# DIOT_template.net
KiCad netlist of a schematic drawn in Altium Designer
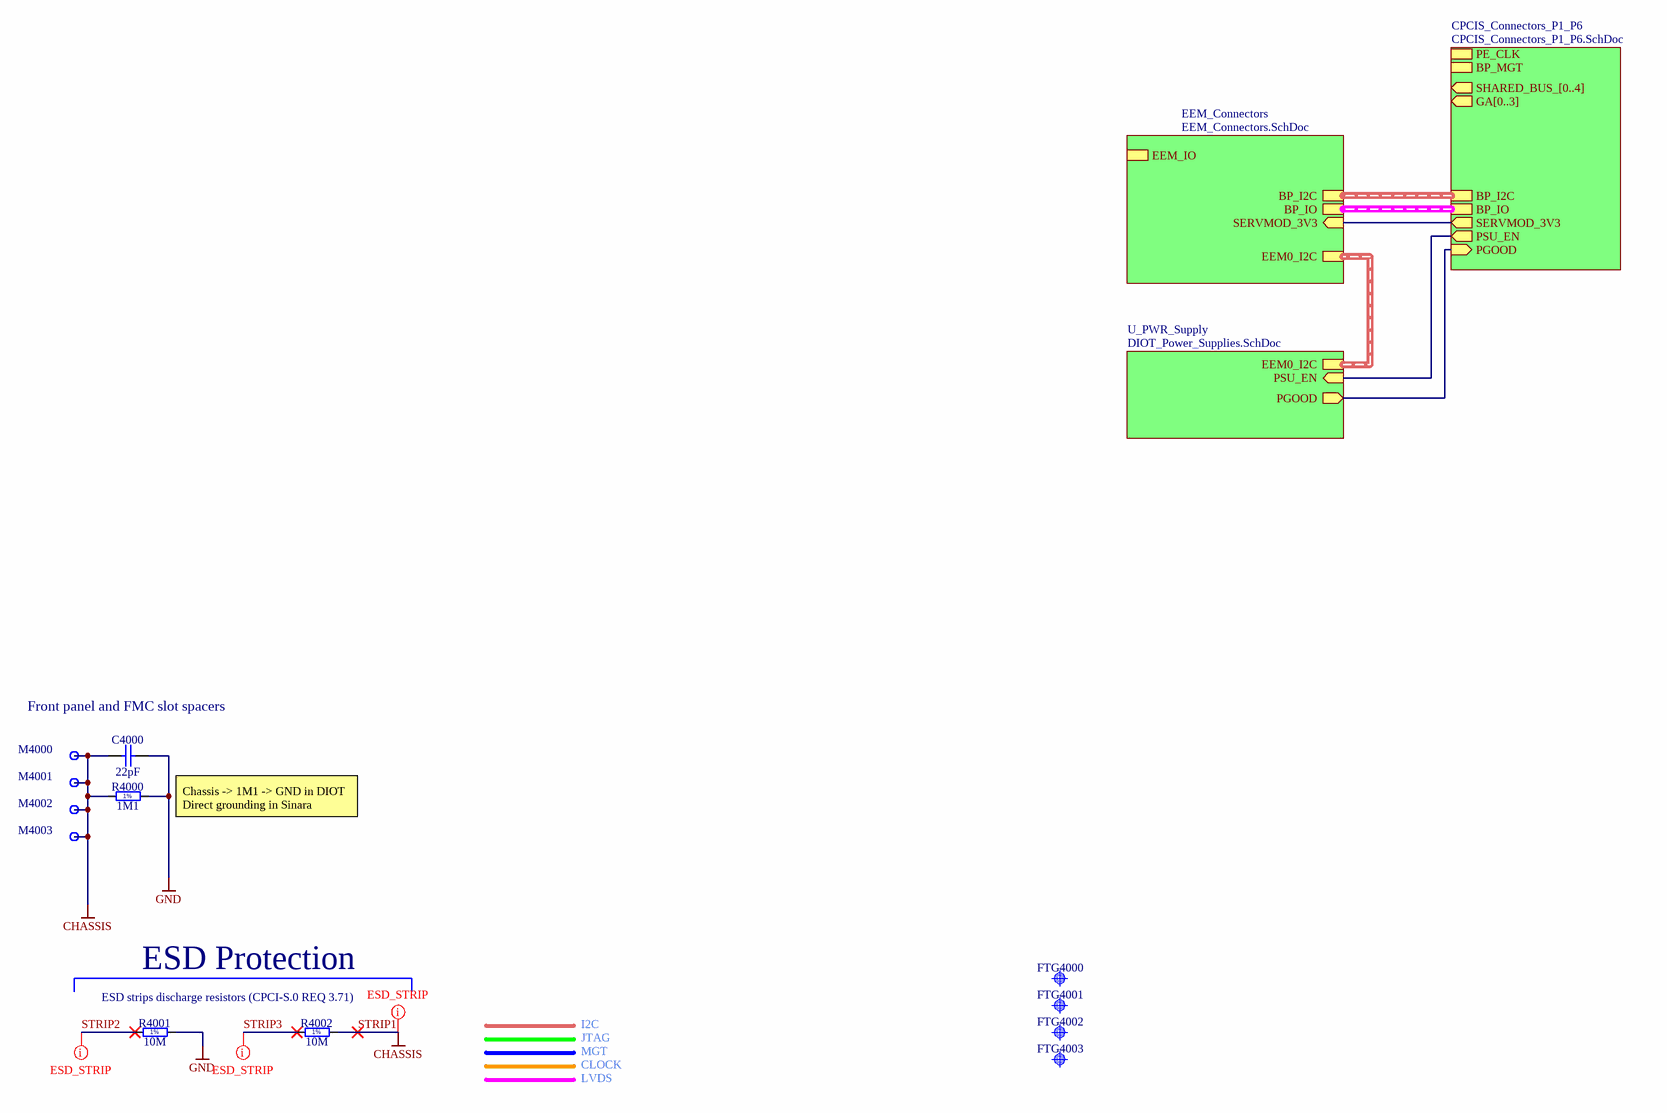
[diagram p0: DIOT_template.SchDoc]

(export (version "E")
  (design (tool "Eeschema 10.0.6"))
  (components
    (comp (ref "C4000")
      (value "22pF")
      (footprint "CAPC1005X55N")
      (description "Non-polarised capacitor")
      (fields
        (field (name "PART NUMBER") "CC0402_22PF_50V_5%_C0G")
        (field (name "VOLTAGE") "50V")
        (field (name "AUTHOR") "CERN DEM JLC")
      )
      (libsource (lib "Capacitors") (part "Capacitor - non polarized"))
    )
    (comp (ref "FTG4000")
      (value "Use only in PCB")
      (footprint "FIDUCIAL_TOP_C100-200")
      (description "Fiducial Target")
      (fields (field (name "PART NUMBER") "FIDUCIAL_TARGET_C100-200") (field (name "AUTHOR") "CERN DEM JLC"))
      (libsource (lib "Eletro-mechanical") (part "Fiducial Target"))
    )
    (comp (ref "FTG4001")
      (value "Use only in PCB")
      (footprint "FIDUCIAL_TOP_S100-200")
      (description "Fiducial Target")
      (fields (field (name "PART NUMBER") "FIDUCIAL_TARGET_S100-200") (field (name "AUTHOR") "CERN DEM JLC"))
      (libsource (lib "Eletro-mechanical") (part "Fiducial Target"))
    )
    (comp (ref "FTG4002")
      (value "Use only in PCB")
      (footprint "FIDUCIAL_TOP_S100-200")
      (description "Fiducial Target")
      (fields (field (name "PART NUMBER") "FIDUCIAL_TARGET_S100-200") (field (name "AUTHOR") "CERN DEM JLC"))
      (libsource (lib "Eletro-mechanical") (part "Fiducial Target"))
    )
    (comp (ref "FTG4003")
      (value "Use only in PCB")
      (footprint "FIDUCIAL_TOP_S100-200")
      (description "Fiducial Target")
      (fields (field (name "PART NUMBER") "FIDUCIAL_TARGET_S100-200") (field (name "AUTHOR") "CERN DEM JLC"))
      (libsource (lib "Eletro-mechanical") (part "Fiducial Target"))
    )
    (comp (ref "M4000")
      (value "Plated Hole")
      (footprint "MTG300_600")
      (description "Single Terminal Socket")
      (fields (field (name "PART NUMBER") "PLATED_HOLE3.0_PAD6.0") (field (name "AUTHOR") "CERN DEM JLC"))
      (libsource (lib "Eletro-mechanical") (part "Single Terminal Socket"))
    )
    (comp (ref "M4001")
      (value "Plated Hole")
      (footprint "MTG300_600")
      (description "Single Terminal Socket")
      (fields (field (name "PART NUMBER") "PLATED_HOLE3.0_PAD6.0") (field (name "AUTHOR") "CERN DEM JLC"))
      (libsource (lib "Eletro-mechanical") (part "Single Terminal Socket"))
    )
    (comp (ref "M4002")
      (value "Plated Hole")
      (footprint "MTG300_600")
      (description "Single Terminal Socket")
      (fields (field (name "PART NUMBER") "PLATED_HOLE3.0_PAD6.0") (field (name "AUTHOR") "CERN DEM JLC"))
      (libsource (lib "Eletro-mechanical") (part "Single Terminal Socket"))
    )
    (comp (ref "M4003")
      (value "Plated Hole")
      (footprint "MTG300_600")
      (description "Single Terminal Socket")
      (fields (field (name "PART NUMBER") "PLATED_HOLE3.0_PAD6.0") (field (name "AUTHOR") "CERN DEM JLC"))
      (libsource (lib "Eletro-mechanical") (part "Single Terminal Socket"))
    )
    (comp (ref "R4000")
      (value "1M1")
      (footprint "RESC2012X60N")
      (description "Resistor - 1%")
      (fields
        (field (name "PART NUMBER") "R0805_1M1_1%_0.125W_100PPM")
        (field (name "MANUFACTURER") "GENERIC")
        (field (name "AUTHOR") "CERN DEM JLC")
      )
      (libsource (lib "Resistors") (part "Resistor - 1%"))
    )
    (comp (ref "R4001")
      (value "10M")
      (footprint "RESC2113X55N")
      (description "Resistor - 1%")
      (fields
        (field (name "PART NUMBER") "R0805_10M_1%_0.125W_100PPM_VISHAY_CRCW e3")
        (field (name "POWER") "0.125W")
        (field (name "AUTHOR") "CERN DEM BC")
      )
      (libsource (lib "Resistors") (part "Resistor - 1%"))
    )
    (comp (ref "R4002")
      (value "10M")
      (footprint "RESC2113X55N")
      (description "Resistor - 1%")
      (fields
        (field (name "PART NUMBER") "R0805_10M_1%_0.125W_100PPM_VISHAY_CRCW e3")
        (field (name "POWER") "0.125W")
        (field (name "AUTHOR") "CERN DEM BC")
      )
      (libsource (lib "Resistors") (part "Resistor - 1%"))
    )
  )
  (nets
    (net (code "13") (name "/STRIP2") (class "Default")
      (node (ref "R4001") (pin "1") (pinfunction "1_1") (pintype "passive+no_connect"))
    )
    (net (code "14") (name "/STRIP3") (class "Default")
      (node (ref "R4002") (pin "1") (pinfunction "1_1") (pintype "passive+no_connect"))
    )
    (net (code "15") (name "CHASSIS") (class "Default")
      (node (ref "C4000") (pin "1") (pinfunction "1_1") (pintype "passive"))
      (node (ref "M4000") (pin "1") (pinfunction "1_1") (pintype "bidirectional"))
      (node (ref "M4001") (pin "1") (pinfunction "1_1") (pintype "bidirectional"))
      (node (ref "M4002") (pin "1") (pinfunction "1_1") (pintype "bidirectional"))
      (node (ref "M4003") (pin "1") (pinfunction "1_1") (pintype "bidirectional"))
      (node (ref "R4000") (pin "1") (pinfunction "1_1") (pintype "passive"))
      (node (ref "R4002") (pin "2") (pinfunction "2_2") (pintype "passive"))
    )
    (net (code "16") (name "GND") (class "Default")
      (node (ref "C4000") (pin "2") (pinfunction "2_2") (pintype "passive"))
      (node (ref "R4000") (pin "2") (pinfunction "2_2") (pintype "passive"))
      (node (ref "R4001") (pin "2") (pinfunction "2_2") (pintype "passive"))
    )
  )
)
